# LFO.net
KiCad netlist of a schematic drawn in Altium Designer
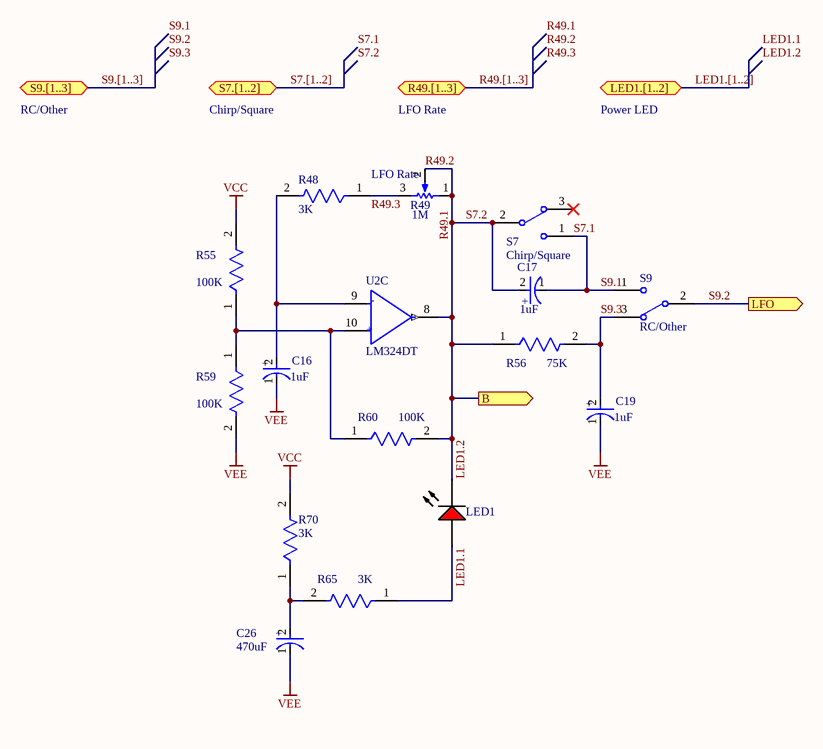
[diagram p0: LFO.SchDoc]

(export (version "E")
  (design (tool "Eeschema 10.0.6"))
  (components
    (comp (ref "C16")
      (value "‎865060640001‎")
      (footprint "FP-OS-CON-SMT-A5-MFG")
      (fields
        (field (name "MANUFACTURER") "Wurth Electronics")
        (field (name "MANUFACTURER PART NUMBER") "865060640001")
        (field (name "TOLERANCE") "20%")
        (field (name "CAPACITANCE") "1uF")
      )
      (libsource (lib "Altium Content Vault") (part "a00bbbee19879c290e62620ae7e47b1"))
    )
    (comp (ref "C17")
      (value "EEE-1HA010NR")
      (footprint "FP-OS-CON-SMT-A5-MFG")
      (description "CAP ALUM POLY 10UF 20% 10V SMD Non-Polarized")
      (fields
        (field (name "MANUFACTURER") "Panasonic")
        (field (name "CAPACITANCE") "1uF")
        (field (name "TOLERANCE") "20%")
      )
      (libsource (lib "Altium Content Vault") (part "a00bbbee19879c290e62620ae7e47b1"))
    )
    (comp (ref "C19")
      (value "‎865060640001‎")
      (footprint "FP-OS-CON-SMT-A5-MFG")
      (fields
        (field (name "MANUFACTURER") "Wurth Electronics")
        (field (name "MANUFACTURER PART NUMBER") "865060640001")
        (field (name "TOLERANCE") "20%")
        (field (name "CAPACITANCE") "1uF")
      )
      (libsource (lib "Altium Content Vault") (part "a00bbbee19879c290e62620ae7e47b1"))
    )
    (comp (ref "C26")
      (value "~")
      (footprint "FP-FTF-MFG")
      (fields
        (field (name "MANUFACTURER") "Wurth Electronics")
        (field (name "MANUFACTURER PART NUMBER") "865080353015")
        (field (name "TOLERANCE") "20%")
        (field (name "CAPACITANCE") "470uF")
      )
      (libsource (lib "Altium Content Vault") (part "a00bbbee19879c290e62620ae7e47b1"))
    )
    (comp (ref "LED1")
      (value "C503B-RAN-CY0B0AA2")
      (footprint "CREE-C503B-RAN")
      (description "Cree(R) 5-mm Red Round LED, 2.1 V, -40 to 100 degC, 2-Pin THD, RoHS, Ammo")
      (fields
        (field (name "MANUFACTURER") "Cree")
        (field (name "MANUFACTURER PART NUMBER") "C503B-RAS-CA0C0AA1")
      )
      (libsource (lib "Altium Content Vault") (part "LED-RED-AK-2"))
    )
    (comp (ref "R48")
      (value "ESR03EZPJ302")
      (footprint "FP-ESR03-IPC_B")
      (description "3kΩ ±5% 0.25W 0603 Anti-Surge Chip Resistor AEC-Q200")
      (fields (field (name "RESISTANCE") "3K") (field (name "TOLERANCE") "5%"))
      (libsource (lib "Altium Content Vault") (part "1029c3af85768c4190bb7ad29bc67b5"))
    )
    (comp (ref "R49")
      (value "LFO Rate")
      (footprint "VR5")
      (description "Potentiometer")
      (fields (field (name "ALTIUM_VALUE") "1M") (field (name "PUBLISHER") "Altium Limited"))
      (libsource (lib "Miscellaneous Devices") (part "RPot"))
    )
    (comp (ref "R55")
      (value "ESR03EZPJ104")
      (footprint "FP-ESR03-IPC_B")
      (description "100kΩ ±5% 0.25W 0603 Anti-Surge Chip Resistor AEC-Q200")
      (fields (field (name "TOLERANCE") "5%") (field (name "RESISTANCE") "100K"))
      (libsource (lib "Altium Content Vault") (part "1029c3af85768c4190bb7ad29bc67b5"))
    )
    (comp (ref "R56")
      (value "ESR03EZPJ753")
      (footprint "FP-ESR03-IPC_B")
      (description "75kΩ ±5% 0.25W 0603 Anti-Surge Chip Resistor AEC-Q200")
      (fields (field (name "TOLERANCE") "5%") (field (name "RESISTANCE") "75K"))
      (libsource (lib "Altium Content Vault") (part "1029c3af85768c4190bb7ad29bc67b5"))
    )
    (comp (ref "R59")
      (value "ESR03EZPJ104")
      (footprint "FP-ESR03-IPC_B")
      (description "100kΩ ±5% 0.25W 0603 Anti-Surge Chip Resistor AEC-Q200")
      (fields (field (name "TOLERANCE") "5%") (field (name "RESISTANCE") "100K"))
      (libsource (lib "Altium Content Vault") (part "1029c3af85768c4190bb7ad29bc67b5"))
    )
    (comp (ref "R60")
      (value "ESR03EZPJ104")
      (footprint "FP-ESR03-IPC_B")
      (description "100kΩ ±5% 0.25W 0603 Anti-Surge Chip Resistor AEC-Q200")
      (fields (field (name "TOLERANCE") "5%") (field (name "RESISTANCE") "100K"))
      (libsource (lib "Altium Content Vault") (part "1029c3af85768c4190bb7ad29bc67b5"))
    )
    (comp (ref "R65")
      (value "ESR03EZPJ302")
      (footprint "FP-ESR03-IPC_B")
      (description "3kΩ ±5% 0.25W 0603 Anti-Surge Chip Resistor AEC-Q200")
      (fields (field (name "RESISTANCE") "3K") (field (name "TOLERANCE") "5%"))
      (libsource (lib "Altium Content Vault") (part "1029c3af85768c4190bb7ad29bc67b5"))
    )
    (comp (ref "R70")
      (value "ESR03EZPJ302")
      (footprint "FP-ESR03-IPC_B")
      (description "3kΩ ±5% 0.25W 0603 Anti-Surge Chip Resistor AEC-Q200")
      (fields (field (name "RESISTANCE") "3K") (field (name "TOLERANCE") "5%"))
      (libsource (lib "Altium Content Vault") (part "1029c3af85768c4190bb7ad29bc67b5"))
    )
    (comp (ref "S7")
      (value "Chirp/Square")
      (footprint "HDR1X3")
      (description "Switch Toggle ON None ON SPDT Round Lever Solder Lug 5A 250VAC 28VDC Panel Mount with Threads")
      (fields
        (field (name "MANUFACTURER") "E-Switch")
        (field (name "MANUFACTURER PART NUMBER") "100SP1T1B1M1QEH")
      )
      (libsource (lib "Miscellaneous Devices") (part "SW-SPDT"))
    )
    (comp (ref "S9")
      (value "RC/Other")
      (footprint "HDR1X3")
      (description "Switch Toggle ON None ON SPDT Round Lever Solder Lug 5A 250VAC 28VDC Panel Mount with Threads")
      (fields
        (field (name "MANUFACTURER") "E-Switch")
        (field (name "MANUFACTURER PART NUMBER") "100SP1T1B1M1QEH")
      )
      (libsource (lib "Miscellaneous Devices") (part "SW-SPDT"))
    )
    (comp (ref "U2")
      (value "LM324DT")
      (footprint "FP-SO-14-MFG")
      (description "IC OPAMP GP 4 CIRCUIT 14SO")
      (fields
        (field (name "OCTOPART") "https://octopart.com/lm324dt-stmicroelectronics-39579146")
        (field (name "MANUFACTURER") "STMicroelectronics")
      )
      (libsource (lib "Altium Content Vault") (part "a065ef67e5aa9ef3942d43d6008d043"))
    )
  )
  (nets
    (net (code "1") (name "/LED1.1") (class "Default")
      (node (ref "LED1") (pin "1") (pinfunction "A_1") (pintype "passive"))
      (node (ref "R65") (pin "1") (pinfunction "1_1") (pintype "passive"))
    )
    (net (code "3") (name "/R49.2") (class "Default")
      (node (ref "C17") (pin "2") (pinfunction "A_2") (pintype "passive"))
      (node (ref "LED1") (pin "2") (pinfunction "K_2") (pintype "passive"))
      (node (ref "R49") (pin "1") (pinfunction "TOP_1") (pintype "passive"))
      (node (ref "R49") (pin "2") (pinfunction "TAP_2") (pintype "passive"))
      (node (ref "R56") (pin "1") (pinfunction "1_1") (pintype "passive"))
      (node (ref "R60") (pin "2") (pinfunction "2_2") (pintype "passive"))
      (node (ref "S7") (pin "2") (pinfunction "2_2") (pintype "passive"))
      (node (ref "U2") (pin "8") (pinfunction "Output_3_8") (pintype "output"))
    )
    (net (code "4") (name "/R49.3") (class "Default")
      (node (ref "R48") (pin "1") (pinfunction "1_1") (pintype "passive"))
      (node (ref "R49") (pin "3") (pinfunction "BOT_3") (pintype "passive"))
    )
    (net (code "6") (name "/S7.1") (class "Default")
      (node (ref "C17") (pin "1") (pinfunction "C_1") (pintype "passive"))
      (node (ref "S7") (pin "1") (pinfunction "1_1") (pintype "passive"))
      (node (ref "S9") (pin "1") (pinfunction "1_1") (pintype "passive"))
    )
    (net (code "8") (name "/S9.2") (class "Default")
      (node (ref "S9") (pin "2") (pinfunction "2_2") (pintype "passive"))
    )
    (net (code "9") (name "/S9.3") (class "Default")
      (node (ref "C19") (pin "2") (pinfunction "A_2") (pintype "passive"))
      (node (ref "R56") (pin "2") (pinfunction "2_2") (pintype "passive"))
      (node (ref "S9") (pin "3") (pinfunction "3_3") (pintype "passive"))
    )
    (net (code "11") (name "Net-(C16-A)") (class "Default")
      (node (ref "C16") (pin "2") (pinfunction "A_2") (pintype "passive"))
      (node (ref "R48") (pin "2") (pinfunction "2_2") (pintype "passive"))
      (node (ref "U2") (pin "9") (pinfunction "Inverting_Input_3_9") (pintype "tri_state"))
    )
    (net (code "12") (name "Net-(C26-A)") (class "Default")
      (node (ref "C26") (pin "2") (pinfunction "A_2") (pintype "passive"))
      (node (ref "R65") (pin "2") (pinfunction "2_2") (pintype "passive"))
      (node (ref "R70") (pin "1") (pinfunction "1_1") (pintype "passive"))
    )
    (net (code "13") (name "Net-(U2C-Non-Inverting_Input_3)") (class "Default")
      (node (ref "R55") (pin "1") (pinfunction "1_1") (pintype "passive"))
      (node (ref "R59") (pin "1") (pinfunction "1_1") (pintype "passive"))
      (node (ref "R60") (pin "1") (pinfunction "1_1") (pintype "passive"))
      (node (ref "U2") (pin "10") (pinfunction "Non-Inverting_Input_3_10") (pintype "tri_state"))
    )
    (net (code "14") (name "VCC") (class "Default")
      (node (ref "R55") (pin "2") (pinfunction "2_2") (pintype "passive"))
      (node (ref "R70") (pin "2") (pinfunction "2_2") (pintype "passive"))
    )
    (net (code "15") (name "VEE") (class "Default")
      (node (ref "C16") (pin "1") (pinfunction "C_1") (pintype "passive"))
      (node (ref "C19") (pin "1") (pinfunction "C_1") (pintype "passive"))
      (node (ref "C26") (pin "1") (pinfunction "C_1") (pintype "passive"))
      (node (ref "R59") (pin "2") (pinfunction "2_2") (pintype "passive"))
    )
    (net (code "16") (name "unconnected-(S7-Pad3)") (class "Default")
      (node (ref "S7") (pin "3") (pinfunction "3_3") (pintype "passive+no_connect"))
    )
  )
)
